# Logic_Power.net
KiCad netlist of a schematic drawn in Altium Designer
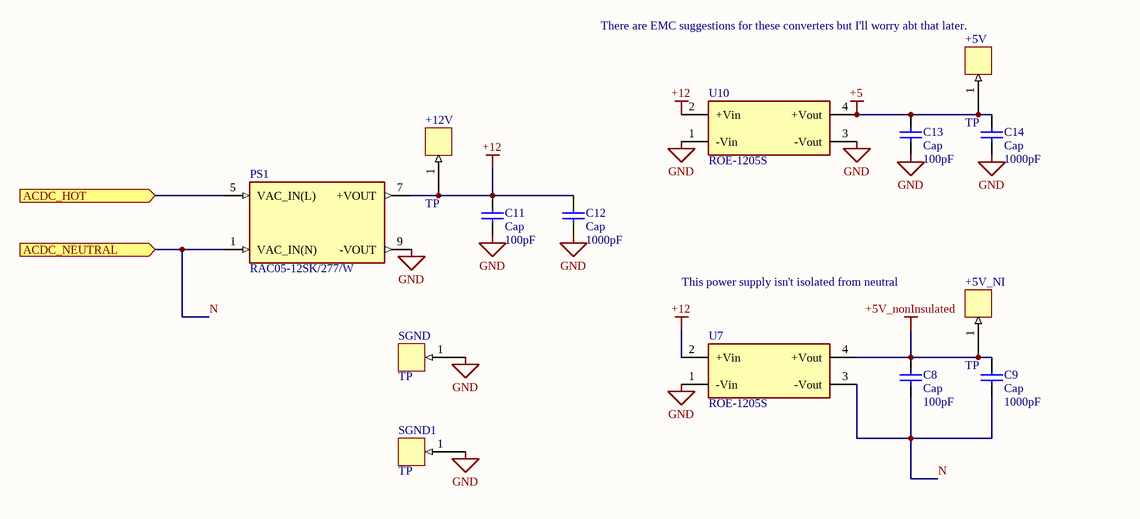
[diagram p0: Logic_Power.SchDoc]

(export (version "E")
  (design (tool "Eeschema 10.0.6"))
  (components
    (comp (ref "+5V") (value "TP") (footprint "TP") (libsource (lib "") (part "TP_1")))
    (comp (ref "+5V_NI") (value "TP") (footprint "TP") (libsource (lib "") (part "TP_1")))
    (comp (ref "+12V") (value "TP") (footprint "TP") (libsource (lib "") (part "TP_1")))
    (comp (ref "C8")
      (value "Cap")
      (footprint "0603")
      (description "Capacitor")
      (fields (field (name "ALTIUM_VALUE") "100pF") (field (name "PUBLISHER") "Altium Limited"))
      (libsource (lib "Miscellaneous Devices") (part "Cap"))
    )
    (comp (ref "C9")
      (value "Cap")
      (footprint "0603")
      (description "Capacitor")
      (fields (field (name "ALTIUM_VALUE") "1000pF") (field (name "PUBLISHER") "Altium Limited"))
      (libsource (lib "Miscellaneous Devices") (part "Cap"))
    )
    (comp (ref "C11")
      (value "Cap")
      (footprint "0603")
      (description "Capacitor")
      (fields (field (name "ALTIUM_VALUE") "100pF") (field (name "PUBLISHER") "Altium Limited"))
      (libsource (lib "Miscellaneous Devices") (part "Cap"))
    )
    (comp (ref "C12")
      (value "Cap")
      (footprint "0603")
      (description "Capacitor")
      (fields (field (name "ALTIUM_VALUE") "1000pF") (field (name "PUBLISHER") "Altium Limited"))
      (libsource (lib "Miscellaneous Devices") (part "Cap"))
    )
    (comp (ref "C13")
      (value "Cap")
      (footprint "0603")
      (description "Capacitor")
      (fields (field (name "ALTIUM_VALUE") "100pF") (field (name "PUBLISHER") "Altium Limited"))
      (libsource (lib "Miscellaneous Devices") (part "Cap"))
    )
    (comp (ref "C14")
      (value "Cap")
      (footprint "0603")
      (description "Capacitor")
      (fields (field (name "ALTIUM_VALUE") "1000pF") (field (name "PUBLISHER") "Altium Limited"))
      (libsource (lib "Miscellaneous Devices") (part "Cap"))
    )
    (comp (ref "PS1")
      (value "RAC05-12SK/277/W")
      (footprint "CONV_RAC05-12SK/277/W")
      (description "5W AC/DC-Converter 'POWERLINE' W 4kV reg")
      (fields (field (name "MF") "Recom Power"))
      (libsource (lib "RAC05-12SK") (part "RAC05-12SK/277/W"))
    )
    (comp (ref "SGND") (value "TP") (footprint "TP") (libsource (lib "TestPoint") (part "TP")))
    (comp (ref "SGND1") (value "TP") (footprint "TP") (libsource (lib "TestPoint") (part "TP")))
    (comp (ref "U7")
      (value "ROE-1205S")
      (footprint "FP-ROE-0505S-MFG")
      (description "DC DC CONVERTER 5V 1W")
      (libsource (lib "Altium Content Vault") (part "f84a8806c6f56f2c85fcd88f8f29d0f"))
    )
    (comp (ref "U10")
      (value "ROE-1205S")
      (footprint "FP-ROE-0505S-MFG")
      (description "DC DC CONVERTER 5V 1W")
      (libsource (lib "Altium Content Vault") (part "f84a8806c6f56f2c85fcd88f8f29d0f"))
    )
  )
  (nets
    (net (code "1") (name "+5") (class "Default")
      (node (ref "+5V") (pin "1") (pintype "input"))
      (node (ref "C13") (pin "2") (pinfunction "2_2") (pintype "passive"))
      (node (ref "C14") (pin "2") (pinfunction "2_2") (pintype "passive"))
      (node (ref "U10") (pin "4") (pinfunction "+Vout_4") (pintype "power_in"))
    )
    (net (code "2") (name "+5V_nonInsulated") (class "Default")
      (node (ref "+5V_NI") (pin "1") (pintype "input"))
      (node (ref "C8") (pin "2") (pinfunction "2_2") (pintype "passive"))
      (node (ref "C9") (pin "2") (pinfunction "2_2") (pintype "passive"))
      (node (ref "U7") (pin "4") (pinfunction "+Vout_4") (pintype "power_in"))
    )
    (net (code "3") (name "+12") (class "Default")
      (node (ref "+12V") (pin "1") (pintype "input"))
      (node (ref "C11") (pin "2") (pinfunction "2_2") (pintype "passive"))
      (node (ref "C12") (pin "2") (pinfunction "2_2") (pintype "passive"))
      (node (ref "PS1") (pin "7") (pinfunction "+VOUT_7") (pintype "output"))
      (node (ref "U10") (pin "2") (pinfunction "+Vin_2") (pintype "power_in"))
      (node (ref "U7") (pin "2") (pinfunction "+Vin_2") (pintype "power_in"))
    )
    (net (code "4") (name "/ACDC_HOT") (class "Default")
      (node (ref "PS1") (pin "5") (pinfunction "VAC_IN(L)_5") (pintype "input"))
    )
    (net (code "5") (name "/N") (class "Default")
      (node (ref "C8") (pin "1") (pinfunction "1_1") (pintype "passive"))
      (node (ref "C9") (pin "1") (pinfunction "1_1") (pintype "passive"))
      (node (ref "PS1") (pin "1") (pinfunction "VAC_IN(N)_1") (pintype "input"))
      (node (ref "U7") (pin "3") (pinfunction "-Vout_3") (pintype "power_in"))
    )
    (net (code "6") (name "GND") (class "Default")
      (node (ref "C11") (pin "1") (pinfunction "1_1") (pintype "passive"))
      (node (ref "C12") (pin "1") (pinfunction "1_1") (pintype "passive"))
      (node (ref "C13") (pin "1") (pinfunction "1_1") (pintype "passive"))
      (node (ref "C14") (pin "1") (pinfunction "1_1") (pintype "passive"))
      (node (ref "PS1") (pin "9") (pinfunction "-VOUT_9") (pintype "output"))
      (node (ref "SGND") (pin "1") (pintype "input"))
      (node (ref "SGND1") (pin "1") (pintype "input"))
      (node (ref "U10") (pin "1") (pinfunction "-Vin_1") (pintype "power_in"))
      (node (ref "U10") (pin "3") (pinfunction "-Vout_3") (pintype "power_in"))
      (node (ref "U7") (pin "1") (pinfunction "-Vin_1") (pintype "power_in"))
    )
  )
)
